# Charger_Main_Power.net
KiCad netlist of a schematic drawn in Altium Designer
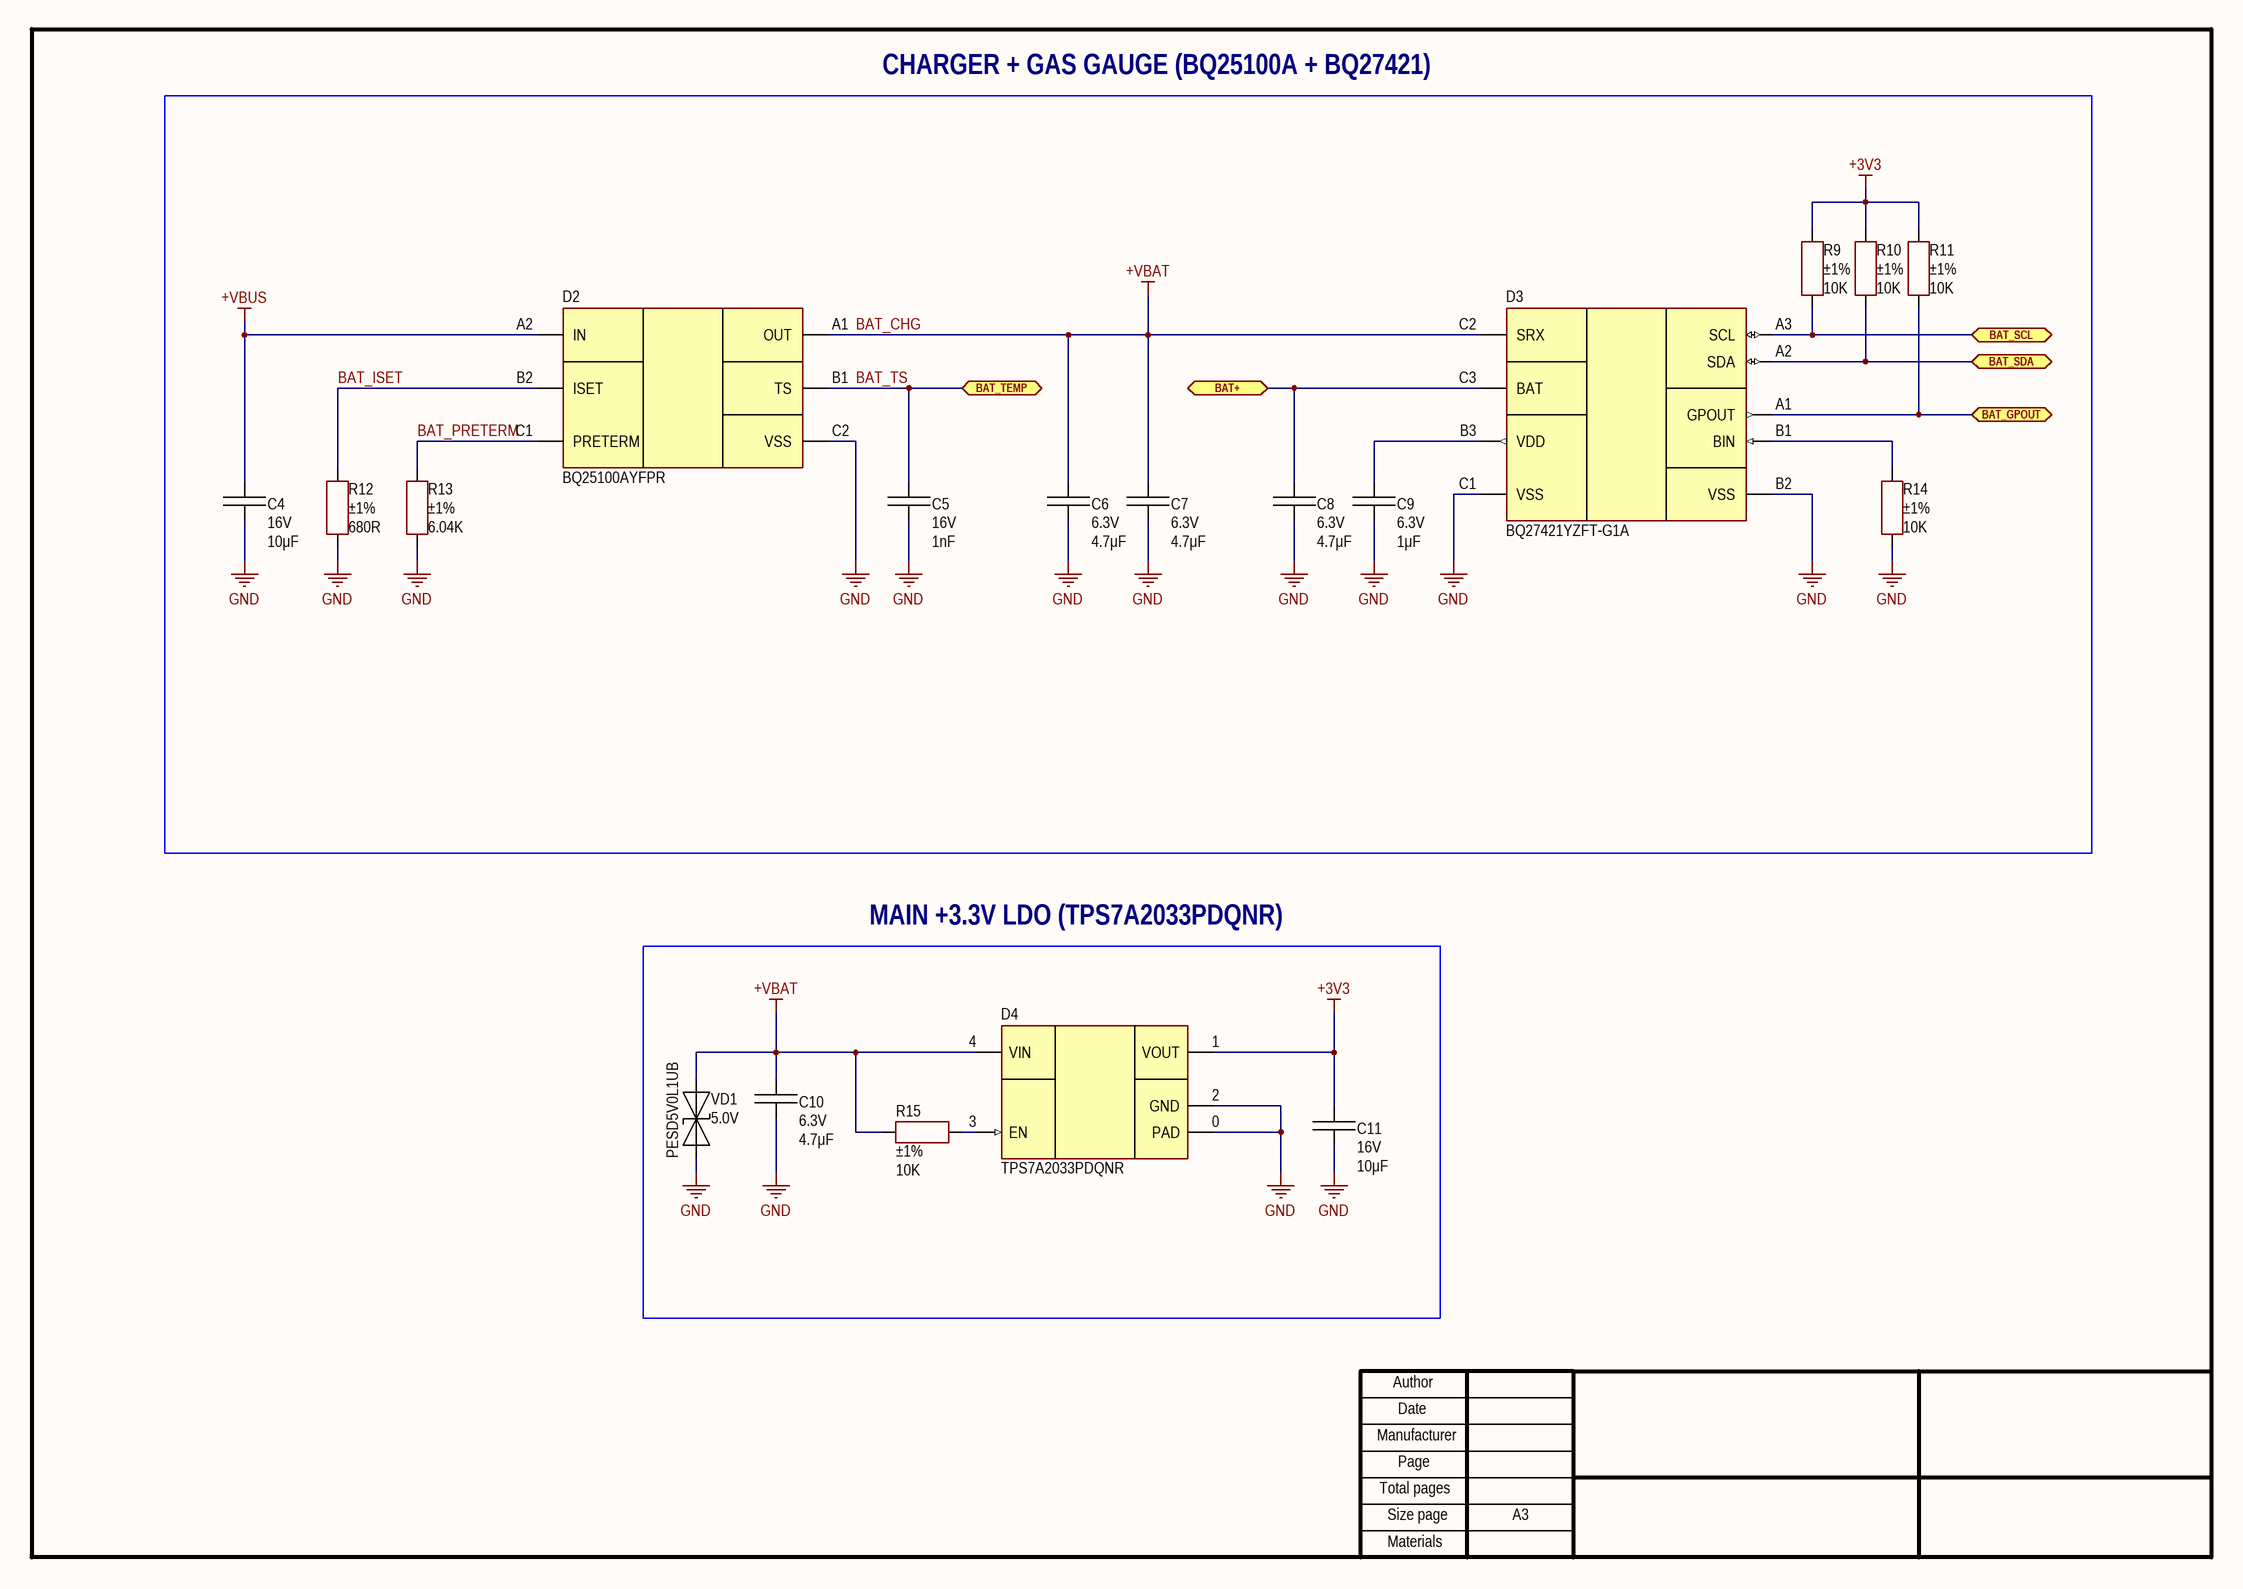
[diagram p0: Charger+Main_Power.SchDoc]

(export (version "E")
  (design (tool "Eeschema 10.0.6"))
  (components
    (comp (ref "C4")
      (value "10μF")
      (footprint "CAP: 0805_NO_SILK")
      (description "10 µF ±20% 16V Ceramic Capacitor X7R 0805 (2012 Metric)")
      (fields
        (field (name "MANUFACTURER") "Yageo")
        (field (name "PARTNUMBER") "CC0805MKX7R7BB106")
        (field (name "VOLTAGE") "16V")
      )
      (libsource (lib "capacitor") (part "Ceramic_0805"))
    )
    (comp (ref "C5")
      (value "1nF")
      (footprint "CAP: 0201")
      (description "1000 pF ±10% 16V Ceramic Capacitor X7R 0201 (0603 Metric)")
      (fields
        (field (name "MANUFACTURER") "Yageo")
        (field (name "PARTNUMBER") "CC0201KRX7R7BB102")
        (field (name "VOLTAGE") "16V")
      )
      (libsource (lib "capacitor") (part "Ceramic_0201"))
    )
    (comp (ref "C6")
      (value "4.7μF")
      (footprint "CAP: 0603_NO_SILK")
      (description "4.7 µF ±20% 6.3V Ceramic Capacitor X7R 0603 (1608 Metric)")
      (fields
        (field (name "MANUFACTURER") "Yageo")
        (field (name "PARTNUMBER") "CC0603MRX7R5BB475")
        (field (name "VOLTAGE") "6.3V")
      )
      (libsource (lib "capacitor") (part "Ceramic_0603"))
    )
    (comp (ref "C7")
      (value "4.7μF")
      (footprint "CAP: 0603_NO_SILK")
      (description "4.7 µF ±20% 6.3V Ceramic Capacitor X7R 0603 (1608 Metric)")
      (fields
        (field (name "MANUFACTURER") "Yageo")
        (field (name "PARTNUMBER") "CC0603MRX7R5BB475")
        (field (name "VOLTAGE") "6.3V")
      )
      (libsource (lib "capacitor") (part "Ceramic_0603"))
    )
    (comp (ref "C8")
      (value "4.7μF")
      (footprint "CAP: 0603_NO_SILK")
      (description "4.7 µF ±20% 6.3V Ceramic Capacitor X7R 0603 (1608 Metric)")
      (fields
        (field (name "MANUFACTURER") "Yageo")
        (field (name "PARTNUMBER") "CC0603MRX7R5BB475")
        (field (name "VOLTAGE") "6.3V")
      )
      (libsource (lib "capacitor") (part "Ceramic_0603"))
    )
    (comp (ref "C9")
      (value "1μF")
      (footprint "CAP: 0402_NO_SILK")
      (description "1 µF ±10% 6.3V Ceramic Capacitor X7R 0402 (1005 Metric)")
      (fields
        (field (name "MANUFACTURER") "Yageo")
        (field (name "PARTNUMBER") "CC0402KRX7R5BB105")
        (field (name "VOLTAGE") "6.3V")
      )
      (libsource (lib "capacitor") (part "Ceramic_0402"))
    )
    (comp (ref "C10")
      (value "4.7μF")
      (footprint "CAP: 0603_NO_SILK")
      (description "4.7 µF ±20% 6.3V Ceramic Capacitor X7R 0603 (1608 Metric)")
      (fields
        (field (name "MANUFACTURER") "Yageo")
        (field (name "PARTNUMBER") "CC0603MRX7R5BB475")
        (field (name "VOLTAGE") "6.3V")
      )
      (libsource (lib "capacitor") (part "Ceramic_0603"))
    )
    (comp (ref "C11")
      (value "10μF")
      (footprint "CAP: 0805_NO_SILK")
      (description "10 µF ±20% 16V Ceramic Capacitor X7R 0805 (2012 Metric)")
      (fields
        (field (name "MANUFACTURER") "Yageo")
        (field (name "PARTNUMBER") "CC0805MKX7R7BB106")
        (field (name "VOLTAGE") "16V")
      )
      (libsource (lib "capacitor") (part "Ceramic_0805"))
    )
    (comp (ref "D2")
      (value "~")
      (footprint "IC: BQ25100")
      (description "PMIC")
      (fields
        (field (name "MANUFACTURER") "Texas Instruments")
        (field (name "VALUEMANUFACTURERPARTNUMBER") "PMIC, Li-Ion/Li-Po, 4.45...6.45V, -40...+85°C, 10-WSON")
        (field (name "PARTNUMBER") "BQ25100AYFPR")
      )
      (libsource (lib "MyLib") (part "BQ25100AYFPR"))
    )
    (comp (ref "D3")
      (value "~")
      (footprint "IC: 9-DSBGA")
      (description "Gas gauge")
      (fields
        (field (name "MANUFACTURER") "Texas Instruments")
        (field (name "VALUEMANUFACTURERPARTNUMBER") "Gas gauge, Li-Ion, 2.45...4.5V, -40...+85°C, 9-DSBGA")
        (field (name "PARTNUMBER") "BQ27421YZFT-G1A")
      )
      (libsource (lib "MyLib") (part "BQ25100AYFPR_1"))
    )
    (comp (ref "D4")
      (value "~")
      (footprint "IC: 4-X2SON")
      (description "Linear voltage regulator")
      (fields
        (field (name "MANUFACTURER") "Texas Instruments")
        (field (name "VALUEMANUFACTURERPARTNUMBER") "Linear voltage regulator, input 3.44...6V, 2V, 3.3V, 0.3A, -40...+125°C, 4-X2SON")
        (field (name "PARTNUMBER") "TPS7A2033PDQNR")
      )
      (libsource (lib "MyLib") (part "TPS7A2033"))
    )
    (comp (ref "R9")
      (value "10K")
      (footprint "RES: 0201")
      (description "10 kOhms ±1% 0.05W, 1/20W Chip Resistor 0201 (0603 Metric) Moisture Resistant Thick Film")
      (fields
        (field (name "MANUFACTURER") "Yageo")
        (field (name "PARTNUMBER") "RC0201JR-0710KL")
        (field (name "TOLERANCE") "±1%")
      )
      (libsource (lib "resistor") (part "Resistor_0201"))
    )
    (comp (ref "R10")
      (value "10K")
      (footprint "RES: 0201")
      (description "10 kOhms ±1% 0.05W, 1/20W Chip Resistor 0201 (0603 Metric) Moisture Resistant Thick Film")
      (fields
        (field (name "MANUFACTURER") "Yageo")
        (field (name "PARTNUMBER") "RC0201JR-0710KL")
        (field (name "TOLERANCE") "±1%")
      )
      (libsource (lib "resistor") (part "Resistor_0201"))
    )
    (comp (ref "R11")
      (value "10K")
      (footprint "RES: 0201")
      (description "10 kOhms ±1% 0.05W, 1/20W Chip Resistor 0201 (0603 Metric) Moisture Resistant Thick Film")
      (fields
        (field (name "MANUFACTURER") "Yageo")
        (field (name "PARTNUMBER") "RC0201JR-0710KL")
        (field (name "TOLERANCE") "±1%")
      )
      (libsource (lib "resistor") (part "Resistor_0201"))
    )
    (comp (ref "R12")
      (value "680R")
      (footprint "RES: 0201")
      (description "680 Ohms ±1% 0.05W, 1/20W Chip Resistor 0201 (0603 Metric) Moisture Resistant Thick Film")
      (fields
        (field (name "MANUFACTURER") "Yageo")
        (field (name "PARTNUMBER") "RC0201FR-07680RL")
        (field (name "TOLERANCE") "±1%")
      )
      (libsource (lib "") (part "Resistor_0201_1"))
    )
    (comp (ref "R13")
      (value "6.04K")
      (footprint "RES: 0201")
      (description "6.04 kOhms ±1% 0.05W, 1/20W Chip Resistor 0201 (0603 Metric) Moisture Resistant Thick Film")
      (fields
        (field (name "MANUFACTURER") "Yageo")
        (field (name "PARTNUMBER") "RC0201FR-076K04L")
        (field (name "TOLERANCE") "±1%")
      )
      (libsource (lib "resistor") (part "Resistor_0201"))
    )
    (comp (ref "R14")
      (value "10K")
      (footprint "RES: 0201")
      (description "10 kOhms ±1% 0.05W, 1/20W Chip Resistor 0201 (0603 Metric) Moisture Resistant Thick Film")
      (fields
        (field (name "MANUFACTURER") "Yageo")
        (field (name "PARTNUMBER") "RC0201JR-0710KL")
        (field (name "TOLERANCE") "±1%")
      )
      (libsource (lib "resistor") (part "Resistor_0201"))
    )
    (comp (ref "R15")
      (value "10K")
      (footprint "RES: 0201")
      (description "10 kOhms ±1% 0.05W, 1/20W Chip Resistor 0201 (0603 Metric) Moisture Resistant Thick Film")
      (fields
        (field (name "MANUFACTURER") "Yageo")
        (field (name "PARTNUMBER") "RC0201JR-0710KL")
        (field (name "TOLERANCE") "±1%")
      )
      (libsource (lib "") (part "Resistor_0201_2"))
    )
    (comp (ref "VD1")
      (value "~")
      (footprint "DIODE: SOD523")
      (description "12V Clamp 3.5A (8/20µs) Ipp Tvs Diode Surface Mount SOD-523")
      (fields
        (field (name "MANUFACTURER") "Nexperia")
        (field (name "VALUEMANUFACTURERPARTNUMBER") "ESD TVS diode, 5.0V, 3.5A, , , SOD-523, -55...+150°C")
        (field (name "VOLTAGE") "5.0V")
        (field (name "PARTNUMBER") "PESD5V0L1UB")
      )
      (libsource (lib "diode") (part "TVS_single"))
    )
  )
  (nets
    (net (code "1") (name "+3V3") (class "Default")
      (node (ref "C11") (pin "2") (pinfunction "2_2") (pintype "passive"))
      (node (ref "D4") (pin "1") (pinfunction "VOUT_1") (pintype "power_in"))
      (node (ref "R10") (pin "2") (pinfunction "2_2") (pintype "passive"))
      (node (ref "R11") (pin "2") (pinfunction "2_2") (pintype "passive"))
      (node (ref "R9") (pin "2") (pinfunction "2_2") (pintype "passive"))
    )
    (net (code "2") (name "+VBAT") (class "Default")
      (node (ref "C10") (pin "2") (pinfunction "2_2") (pintype "passive"))
      (node (ref "C6") (pin "2") (pinfunction "2_2") (pintype "passive"))
      (node (ref "C7") (pin "2") (pinfunction "2_2") (pintype "passive"))
      (node (ref "D2") (pin "A1") (pinfunction "OUT_A1") (pintype "passive"))
      (node (ref "D3") (pin "C2") (pinfunction "SRX_C2") (pintype "power_in"))
      (node (ref "D4") (pin "4") (pinfunction "VIN_4") (pintype "power_in"))
      (node (ref "R15") (pin "2") (pinfunction "2_2") (pintype "passive"))
      (node (ref "VD1") (pin "2") (pinfunction "C_2") (pintype "passive"))
    )
    (net (code "3") (name "+VBUS") (class "Default")
      (node (ref "C4") (pin "2") (pinfunction "2_2") (pintype "passive"))
      (node (ref "D2") (pin "A2") (pinfunction "IN_A2") (pintype "passive"))
    )
    (net (code "4") (name "/BAT+") (class "Default")
      (node (ref "C8") (pin "2") (pinfunction "2_2") (pintype "passive"))
      (node (ref "D3") (pin "C3") (pinfunction "BAT_C3") (pintype "power_in"))
    )
    (net (code "5") (name "/BAT_GPOUT") (class "Default")
      (node (ref "D3") (pin "A1") (pinfunction "GPOUT_A1") (pintype "output"))
      (node (ref "R11") (pin "1") (pinfunction "1_1") (pintype "passive"))
    )
    (net (code "6") (name "/BAT_ISET") (class "Default")
      (node (ref "D2") (pin "B2") (pinfunction "ISET_B2") (pintype "passive"))
      (node (ref "R12") (pin "1") (pinfunction "1_1") (pintype "passive"))
    )
    (net (code "7") (name "/BAT_PRETERM") (class "Default")
      (node (ref "D2") (pin "C1") (pinfunction "PRETERM_C1") (pintype "passive"))
      (node (ref "R13") (pin "2") (pinfunction "2_2") (pintype "passive"))
    )
    (net (code "8") (name "/BAT_SCL") (class "Default")
      (node (ref "D3") (pin "A3") (pinfunction "SCL_A3") (pintype "bidirectional"))
      (node (ref "R9") (pin "1") (pinfunction "1_1") (pintype "passive"))
    )
    (net (code "9") (name "/BAT_SDA") (class "Default")
      (node (ref "D3") (pin "A2") (pinfunction "SDA_A2") (pintype "bidirectional"))
      (node (ref "R10") (pin "1") (pinfunction "1_1") (pintype "passive"))
    )
    (net (code "10") (name "/BAT_TS") (class "Default")
      (node (ref "C5") (pin "2") (pinfunction "2_2") (pintype "passive"))
      (node (ref "D2") (pin "B1") (pinfunction "TS_B1") (pintype "passive"))
    )
    (net (code "11") (name "GND") (class "Default")
      (node (ref "C10") (pin "1") (pinfunction "1_1") (pintype "passive"))
      (node (ref "C11") (pin "1") (pinfunction "1_1") (pintype "passive"))
      (node (ref "C4") (pin "1") (pinfunction "1_1") (pintype "passive"))
      (node (ref "C5") (pin "1") (pinfunction "1_1") (pintype "passive"))
      (node (ref "C6") (pin "1") (pinfunction "1_1") (pintype "passive"))
      (node (ref "C7") (pin "1") (pinfunction "1_1") (pintype "passive"))
      (node (ref "C8") (pin "1") (pinfunction "1_1") (pintype "passive"))
      (node (ref "C9") (pin "1") (pinfunction "1_1") (pintype "passive"))
      (node (ref "D2") (pin "C2") (pinfunction "VSS_C2") (pintype "passive"))
      (node (ref "D3") (pin "B2") (pinfunction "VSS_B2") (pintype "power_in"))
      (node (ref "D3") (pin "C1") (pinfunction "VSS_C1") (pintype "power_in"))
      (node (ref "D4") (pin "0") (pinfunction "PAD_0") (pintype "power_in"))
      (node (ref "D4") (pin "2") (pinfunction "GND_2") (pintype "power_in"))
      (node (ref "R12") (pin "2") (pinfunction "2_2") (pintype "passive"))
      (node (ref "R13") (pin "1") (pinfunction "1_1") (pintype "passive"))
      (node (ref "R14") (pin "1") (pinfunction "1_1") (pintype "passive"))
      (node (ref "VD1") (pin "1") (pinfunction "A_1") (pintype "passive"))
    )
    (net (code "12") (name "Net-(D3-BIN)") (class "Default")
      (node (ref "D3") (pin "B1") (pinfunction "BIN_B1") (pintype "input"))
      (node (ref "R14") (pin "2") (pinfunction "2_2") (pintype "passive"))
    )
    (net (code "13") (name "Net-(D3-VDD)") (class "Default")
      (node (ref "C9") (pin "2") (pinfunction "2_2") (pintype "passive"))
      (node (ref "D3") (pin "B3") (pinfunction "VDD_B3") (pintype "output"))
    )
    (net (code "14") (name "Net-(D4-EN)") (class "Default")
      (node (ref "D4") (pin "3") (pinfunction "EN_3") (pintype "input"))
      (node (ref "R15") (pin "1") (pinfunction "1_1") (pintype "passive"))
    )
  )
)
